# Shield.net
KiCad netlist of a schematic drawn in Altium Designer
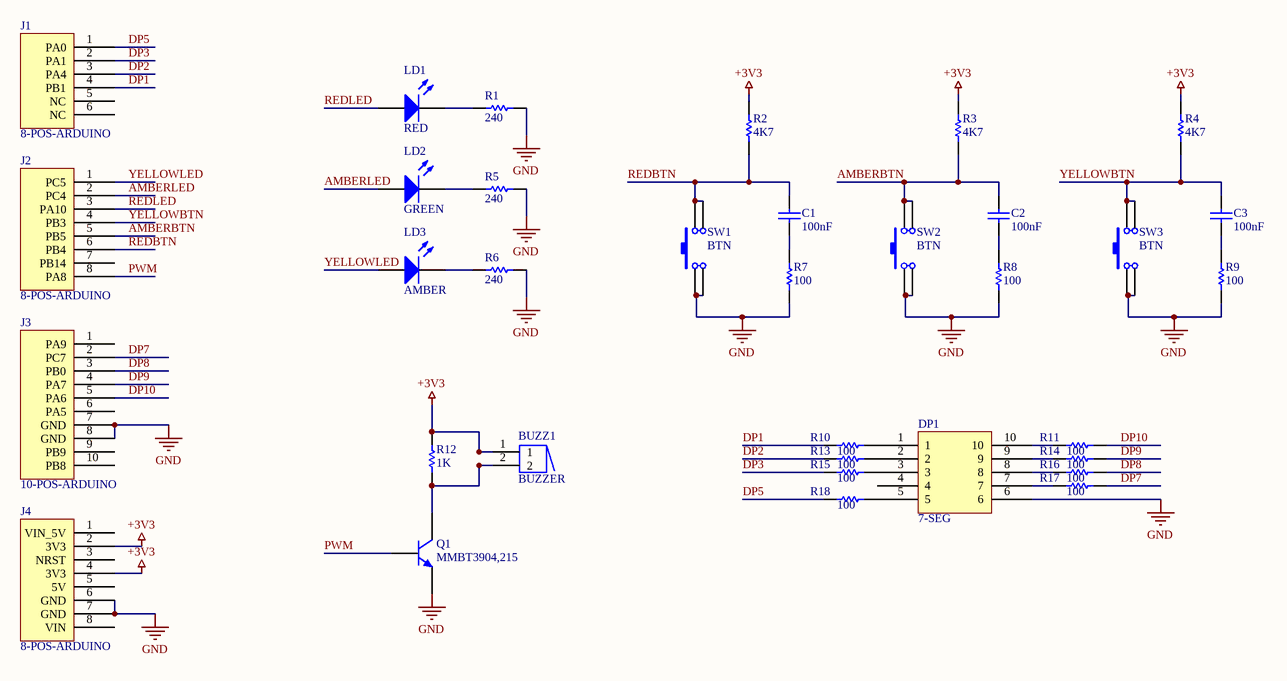
[diagram p0: Shield.SchDoc]

(export (version "E")
  (design (tool "Eeschema 10.0.6"))
  (components
    (comp (ref "BUZZ1")
      (value "BUZZER")
      (footprint "Buzzer")
      (description "AUDIO PIEZO TRANSDUCER 30V TH")
      (fields (field (name "MANUFACTURER") "TDK") (field (name "MANUFACTURER PART NUMBER") "PS1240P02BT"))
      (libsource (lib "Shield") (part "PS1240P02BT"))
    )
    (comp (ref "C1")
      (value "100nF")
      (footprint "CAPCP3225X12N")
      (description "CAP CER 0.1UF 50V X7R 1206")
      (fields
        (field (name "MANUFACTURER") "Yageo")
        (field (name "MANUFACTURER PART NUMBER") "CC1206KRX7R9BB104")
      )
      (libsource (lib "Shield") (part "CC1206KRX7R9BB104"))
    )
    (comp (ref "C2")
      (value "100nF")
      (footprint "CAPCP3225X12N")
      (description "CAP CER 0.1UF 50V X7R 1206")
      (fields
        (field (name "MANUFACTURER") "Yageo")
        (field (name "MANUFACTURER PART NUMBER") "CC1206KRX7R9BB104")
      )
      (libsource (lib "Shield") (part "CC1206KRX7R9BB104"))
    )
    (comp (ref "C3")
      (value "100nF")
      (footprint "CAPCP3225X12N")
      (description "CAP CER 0.1UF 50V X7R 1206")
      (fields
        (field (name "MANUFACTURER") "Yageo")
        (field (name "MANUFACTURER PART NUMBER") "CC1206KRX7R9BB104")
      )
      (libsource (lib "Shield") (part "CC1206KRX7R9BB104"))
    )
    (comp (ref "DP1")
      (value "7-SEG")
      (footprint "7-seg-display")
      (fields
        (field (name "MANUFACTURER") "Inolux")
        (field (name "MANUFACTURER PART NUMBER") "INND-TS40YGCB")
      )
      (libsource (lib "Shield") (part "INND-TS40YGCB"))
    )
    (comp (ref "J1")
      (value "8-POS-ARDUINO")
      (footprint "PIN 6")
      (description "Conn Header Vert 6POS 2.54MM")
      (fields
        (field (name "MANUFACTURER") "Sullins")
        (field (name "MANUFACTURER PART NUMBER") "PREC006SABN-RC")
      )
      (libsource (lib "Shield") (part "PREC006SABN-RC"))
    )
    (comp (ref "J2")
      (value "8-POS-ARDUINO")
      (footprint "PIN 8")
      (description "CONN HEADER VERT 8POS 2.54MM")
      (fields
        (field (name "MANUFACTURER") "Sullins")
        (field (name "MANUFACTURER PART NUMBER") "PREC008SAAN-RC")
      )
      (libsource (lib "Shield") (part "PREC008SAAN-RC"))
    )
    (comp (ref "J3")
      (value "10-POS-ARDUINO")
      (footprint "PIN 10")
      (description "CONN HEADER .100\" SNGL STR 10POS")
      (fields
        (field (name "MANUFACTURER") "Sullins")
        (field (name "MANUFACTURER PART NUMBER") "PREC010SAAN-RC")
      )
      (libsource (lib "Shield") (part "PREC010SAAN-RC"))
    )
    (comp (ref "J4")
      (value "8-POS-ARDUINO")
      (footprint "PIN 8")
      (description "CONN HEADER VERT 8POS 2.54MM")
      (fields
        (field (name "MANUFACTURER") "Sullins")
        (field (name "MANUFACTURER PART NUMBER") "PREC008SAAN-RC")
      )
      (libsource (lib "Shield") (part "PREC008SAAN-RC (2)"))
    )
    (comp (ref "LD1")
      (value "RED")
      (footprint "DIOC3216X21N")
      (description "LED Uni-Color Red 660nm 2-Pin Chip LED T/R")
      (fields
        (field (name "MANUFACTURER") "Vishay Lite-On")
        (field (name "MANUFACTURER PART NUMBER") "LTST-C150CKT")
      )
      (libsource (lib "Shield") (part "LTST-C150CKT"))
    )
    (comp (ref "LD2")
      (value "GREEN")
      (footprint "DIOC3216X21N")
      (description "LED GREEN CLEAR 1206 SMD")
      (fields
        (field (name "MANUFACTURER") "Vishay Lite-On")
        (field (name "MANUFACTURER PART NUMBER") "LTST-C150GKT")
      )
      (libsource (lib "Shield") (part "LTST-C150GKT"))
    )
    (comp (ref "LD3")
      (value "AMBER")
      (footprint "DIOC3216X21N")
      (description "LED AMBER CLEAR 1206 SMD")
      (fields
        (field (name "MANUFACTURER") "Vishay Lite-On")
        (field (name "MANUFACTURER PART NUMBER") "LTST-C150AKT")
      )
      (libsource (lib "Shield") (part "LTST-C150AKT"))
    )
    (comp (ref "Q1")
      (value "MMBT3904,215")
      (footprint "SOT95P230X110-3N")
      (description "TRANS NPN 40V 0.2A SOT23")
      (fields (field (name "MANUFACTURER") "Nexperia"))
      (libsource (lib "Shield") (part "MMBT3904,215"))
    )
    (comp (ref "R1")
      (value "240")
      (footprint "RESC3115X06N")
      (description "Res Thick Film 1206 240 Ohm 1% 0.25W(1/4W) ±100ppm/C Molded SMD Automotive T/R")
      (fields
        (field (name "MANUFACTURER") "Stackpole Electronics")
        (field (name "MANUFACTURER PART NUMBER") "RMCF1206FT240R")
      )
      (libsource (lib "Shield") (part "RMCF1206FT240R"))
    )
    (comp (ref "R2")
      (value "4K7")
      (footprint "RESC3115X06N")
      (description "RES SMD 4.7K OHM 1% 1/4W 1206")
      (fields
        (field (name "MANUFACTURER") "Stackpole Electronics")
        (field (name "MANUFACTURER PART NUMBER") "RMCF1206FT4K70")
      )
      (libsource (lib "Shield") (part "RMCF1206FT4K70"))
    )
    (comp (ref "R3")
      (value "4K7")
      (footprint "RESC3115X06N")
      (description "RES SMD 4.7K OHM 1% 1/4W 1206")
      (fields
        (field (name "MANUFACTURER") "Stackpole Electronics")
        (field (name "MANUFACTURER PART NUMBER") "RMCF1206FT4K70")
      )
      (libsource (lib "Shield") (part "RMCF1206FT4K70"))
    )
    (comp (ref "R4")
      (value "4K7")
      (footprint "RESC3115X06N")
      (description "RES SMD 4.7K OHM 1% 1/4W 1206")
      (fields
        (field (name "MANUFACTURER") "Stackpole Electronics")
        (field (name "MANUFACTURER PART NUMBER") "RMCF1206FT4K70")
      )
      (libsource (lib "Shield") (part "RMCF1206FT4K70"))
    )
    (comp (ref "R5")
      (value "240")
      (footprint "RESC3115X06N")
      (description "Res Thick Film 1206 240 Ohm 1% 0.25W(1/4W) ±100ppm/C Molded SMD Automotive T/R")
      (fields
        (field (name "MANUFACTURER") "Stackpole Electronics")
        (field (name "MANUFACTURER PART NUMBER") "RMCF1206FT240R")
      )
      (libsource (lib "Shield") (part "RMCF1206FT240R"))
    )
    (comp (ref "R6")
      (value "240")
      (footprint "RESC3115X06N")
      (description "Res Thick Film 1206 240 Ohm 1% 0.25W(1/4W) ±100ppm/C Molded SMD Automotive T/R")
      (fields
        (field (name "MANUFACTURER") "Stackpole Electronics")
        (field (name "MANUFACTURER PART NUMBER") "RMCF1206FT240R")
      )
      (libsource (lib "Shield") (part "RMCF1206FT240R"))
    )
    (comp (ref "R7")
      (value "100")
      (footprint "RESC3115X06N")
      (description "RES 100 OHM 1% 1/4W 1206")
      (fields
        (field (name "MANUFACTURER") "Stackpole Electronics")
        (field (name "MANUFACTURER PART NUMBER") "RMCF1206FT100R")
      )
      (libsource (lib "Shield") (part "RMCF1206FT100R"))
    )
    (comp (ref "R8")
      (value "100")
      (footprint "RESC3115X06N")
      (description "RES 100 OHM 1% 1/4W 1206")
      (fields
        (field (name "MANUFACTURER") "Stackpole Electronics")
        (field (name "MANUFACTURER PART NUMBER") "RMCF1206FT100R")
      )
      (libsource (lib "Shield") (part "RMCF1206FT100R"))
    )
    (comp (ref "R9")
      (value "100")
      (footprint "RESC3115X06N")
      (description "RES 100 OHM 1% 1/4W 1206")
      (fields
        (field (name "MANUFACTURER") "Stackpole Electronics")
        (field (name "MANUFACTURER PART NUMBER") "RMCF1206FT100R")
      )
      (libsource (lib "Shield") (part "RMCF1206FT100R"))
    )
    (comp (ref "R10")
      (value "100")
      (footprint "RESC3115X06N")
      (description "RES 100 OHM 1% 1/4W 1206")
      (fields
        (field (name "MANUFACTURER") "Stackpole Electronics")
        (field (name "MANUFACTURER PART NUMBER") "RMCF1206FT100R")
      )
      (libsource (lib "Shield") (part "RMCF1206FT100R"))
    )
    (comp (ref "R11")
      (value "100")
      (footprint "RESC3115X06N")
      (description "RES 100 OHM 1% 1/4W 1206")
      (fields
        (field (name "MANUFACTURER") "Stackpole Electronics")
        (field (name "MANUFACTURER PART NUMBER") "RMCF1206FT100R")
      )
      (libsource (lib "Shield") (part "RMCF1206FT100R"))
    )
    (comp (ref "R12")
      (value "1K")
      (footprint "RESC3115X06N")
      (description "RES 1K OHM 1% 1/2W 1206")
      (fields
        (field (name "MANUFACTURER") "Stackpole Electronics")
        (field (name "MANUFACTURER PART NUMBER") "RNCP1206FTD1K00")
      )
      (libsource (lib "Shield") (part "RNCP1206FTD1K00"))
    )
    (comp (ref "R13")
      (value "100")
      (footprint "RESC3115X06N")
      (description "RES 100 OHM 1% 1/4W 1206")
      (fields
        (field (name "MANUFACTURER") "Stackpole Electronics")
        (field (name "MANUFACTURER PART NUMBER") "RMCF1206FT100R")
      )
      (libsource (lib "Shield") (part "RMCF1206FT100R"))
    )
    (comp (ref "R14")
      (value "100")
      (footprint "RESC3115X06N")
      (description "RES 100 OHM 1% 1/4W 1206")
      (fields
        (field (name "MANUFACTURER") "Stackpole Electronics")
        (field (name "MANUFACTURER PART NUMBER") "RMCF1206FT100R")
      )
      (libsource (lib "Shield") (part "RMCF1206FT100R"))
    )
    (comp (ref "R15")
      (value "100")
      (footprint "RESC3115X06N")
      (description "RES 100 OHM 1% 1/4W 1206")
      (fields
        (field (name "MANUFACTURER") "Stackpole Electronics")
        (field (name "MANUFACTURER PART NUMBER") "RMCF1206FT100R")
      )
      (libsource (lib "Shield") (part "RMCF1206FT100R"))
    )
    (comp (ref "R16")
      (value "100")
      (footprint "RESC3115X06N")
      (description "RES 100 OHM 1% 1/4W 1206")
      (fields
        (field (name "MANUFACTURER") "Stackpole Electronics")
        (field (name "MANUFACTURER PART NUMBER") "RMCF1206FT100R")
      )
      (libsource (lib "Shield") (part "RMCF1206FT100R"))
    )
    (comp (ref "R17")
      (value "100")
      (footprint "RESC3115X06N")
      (description "RES 100 OHM 1% 1/4W 1206")
      (fields
        (field (name "MANUFACTURER") "Stackpole Electronics")
        (field (name "MANUFACTURER PART NUMBER") "RMCF1206FT100R")
      )
      (libsource (lib "Shield") (part "RMCF1206FT100R"))
    )
    (comp (ref "R18")
      (value "100")
      (footprint "RESC3115X06N")
      (description "RES 100 OHM 1% 1/4W 1206")
      (fields
        (field (name "MANUFACTURER") "Stackpole Electronics")
        (field (name "MANUFACTURER PART NUMBER") "RMCF1206FT100R")
      )
      (libsource (lib "Shield") (part "RMCF1206FT100R"))
    )
    (comp (ref "SW1")
      (value "BTN")
      (footprint "Button")
      (description "INWALL LENS COVER , WHITE , 6 (")
      (fields
        (field (name "MANUFACTURER") "ITT C&K")
        (field (name "MANUFACTURER PART NUMBER") "PTS647SK70SMTR2LFS")
      )
      (libsource (lib "Shield") (part "PTS647SK70SMTR2LFS"))
    )
    (comp (ref "SW2")
      (value "BTN")
      (footprint "Button")
      (description "INWALL LENS COVER , WHITE , 6 (")
      (fields
        (field (name "MANUFACTURER") "ITT C&K")
        (field (name "MANUFACTURER PART NUMBER") "PTS647SK70SMTR2LFS")
      )
      (libsource (lib "Shield") (part "PTS647SK70SMTR2LFS"))
    )
    (comp (ref "SW3")
      (value "BTN")
      (footprint "Button")
      (description "INWALL LENS COVER , WHITE , 6 (")
      (fields
        (field (name "MANUFACTURER") "ITT C&K")
        (field (name "MANUFACTURER PART NUMBER") "PTS647SK70SMTR2LFS")
      )
      (libsource (lib "Shield") (part "PTS647SK70SMTR2LFS"))
    )
  )
  (nets
    (net (code "1") (name "+3V3") (class "Default")
      (node (ref "BUZZ1") (pin "1") (pinfunction "1_1") (pintype "passive"))
      (node (ref "J4") (pin "2") (pinfunction "3V3_2") (pintype "passive"))
      (node (ref "J4") (pin "4") (pinfunction "3V3_4") (pintype "passive"))
      (node (ref "R12") (pin "2") (pinfunction "2_2") (pintype "passive"))
      (node (ref "R2") (pin "2") (pinfunction "2_2") (pintype "passive"))
      (node (ref "R3") (pin "2") (pinfunction "2_2") (pintype "passive"))
      (node (ref "R4") (pin "2") (pinfunction "2_2") (pintype "passive"))
    )
    (net (code "2") (name "/AMBERBTN") (class "Default")
      (node (ref "C2") (pin "2") (pinfunction "2_2") (pintype "passive"))
      (node (ref "J2") (pin "5") (pinfunction "PB5_5") (pintype "passive"))
      (node (ref "R3") (pin "1") (pinfunction "1_1") (pintype "passive"))
      (node (ref "SW2") (pin "3") (pinfunction "2_3") (pintype "passive"))
      (node (ref "SW2") (pin "4") (pinfunction "3_4") (pintype "passive"))
    )
    (net (code "3") (name "/AMBERLED") (class "Default")
      (node (ref "J2") (pin "2") (pinfunction "PC4_2") (pintype "passive"))
      (node (ref "LD2") (pin "1") (pinfunction "A_1") (pintype "passive"))
    )
    (net (code "4") (name "/DP1") (class "Default")
      (node (ref "J1") (pin "4") (pinfunction "PB1_4") (pintype "passive"))
      (node (ref "R10") (pin "2") (pinfunction "2_2") (pintype "passive"))
    )
    (net (code "5") (name "/DP2") (class "Default")
      (node (ref "J1") (pin "3") (pinfunction "PA4_3") (pintype "passive"))
      (node (ref "R13") (pin "2") (pinfunction "2_2") (pintype "passive"))
    )
    (net (code "6") (name "/DP3") (class "Default")
      (node (ref "J1") (pin "2") (pinfunction "PA1_2") (pintype "passive"))
      (node (ref "R15") (pin "2") (pinfunction "2_2") (pintype "passive"))
    )
    (net (code "7") (name "/DP5") (class "Default")
      (node (ref "J1") (pin "1") (pinfunction "PA0_1") (pintype "passive"))
      (node (ref "R18") (pin "2") (pinfunction "2_2") (pintype "passive"))
    )
    (net (code "8") (name "/DP7") (class "Default")
      (node (ref "J3") (pin "2") (pinfunction "PC7_2") (pintype "passive"))
      (node (ref "R17") (pin "1") (pinfunction "1_1") (pintype "passive"))
    )
    (net (code "9") (name "/DP8") (class "Default")
      (node (ref "J3") (pin "3") (pinfunction "PB0_3") (pintype "passive"))
      (node (ref "R16") (pin "1") (pinfunction "1_1") (pintype "passive"))
    )
    (net (code "10") (name "/DP9") (class "Default")
      (node (ref "J3") (pin "4") (pinfunction "PA7_4") (pintype "passive"))
      (node (ref "R14") (pin "1") (pinfunction "1_1") (pintype "passive"))
    )
    (net (code "11") (name "/DP10") (class "Default")
      (node (ref "J3") (pin "5") (pinfunction "PA6_5") (pintype "passive"))
      (node (ref "R11") (pin "1") (pinfunction "1_1") (pintype "passive"))
    )
    (net (code "12") (name "/PWM") (class "Default")
      (node (ref "J2") (pin "8") (pinfunction "PA8_8") (pintype "passive"))
      (node (ref "Q1") (pin "1") (pinfunction "B_1") (pintype "passive"))
    )
    (net (code "13") (name "/REDBTN") (class "Default")
      (node (ref "C1") (pin "2") (pinfunction "2_2") (pintype "passive"))
      (node (ref "J2") (pin "6") (pinfunction "PB4_6") (pintype "passive"))
      (node (ref "R2") (pin "1") (pinfunction "1_1") (pintype "passive"))
      (node (ref "SW1") (pin "3") (pinfunction "2_3") (pintype "passive"))
      (node (ref "SW1") (pin "4") (pinfunction "3_4") (pintype "passive"))
    )
    (net (code "14") (name "/REDLED") (class "Default")
      (node (ref "J2") (pin "3") (pinfunction "PA10_3") (pintype "passive"))
      (node (ref "LD1") (pin "1") (pinfunction "A_1") (pintype "passive"))
    )
    (net (code "15") (name "/YELLOWBTN") (class "Default")
      (node (ref "C3") (pin "2") (pinfunction "2_2") (pintype "passive"))
      (node (ref "J2") (pin "4") (pinfunction "PB3_4") (pintype "passive"))
      (node (ref "R4") (pin "1") (pinfunction "1_1") (pintype "passive"))
      (node (ref "SW3") (pin "3") (pinfunction "2_3") (pintype "passive"))
      (node (ref "SW3") (pin "4") (pinfunction "3_4") (pintype "passive"))
    )
    (net (code "16") (name "/YELLOWLED") (class "Default")
      (node (ref "J2") (pin "1") (pinfunction "PC5_1") (pintype "passive"))
      (node (ref "LD3") (pin "1") (pinfunction "A_1") (pintype "passive"))
    )
    (net (code "17") (name "GND") (class "Default")
      (node (ref "DP1") (pin "6") (pinfunction "6_6") (pintype "passive"))
      (node (ref "J3") (pin "7") (pinfunction "GND_7") (pintype "passive"))
      (node (ref "J3") (pin "8") (pinfunction "GND_8") (pintype "passive"))
      (node (ref "J4") (pin "6") (pinfunction "GND_6") (pintype "passive"))
      (node (ref "J4") (pin "7") (pinfunction "GND_7") (pintype "passive"))
      (node (ref "Q1") (pin "2") (pinfunction "E_2") (pintype "passive"))
      (node (ref "R1") (pin "2") (pinfunction "2_2") (pintype "passive"))
      (node (ref "R5") (pin "2") (pinfunction "2_2") (pintype "passive"))
      (node (ref "R6") (pin "2") (pinfunction "2_2") (pintype "passive"))
      (node (ref "R7") (pin "1") (pinfunction "1_1") (pintype "passive"))
      (node (ref "R8") (pin "1") (pinfunction "1_1") (pintype "passive"))
      (node (ref "R9") (pin "1") (pinfunction "1_1") (pintype "passive"))
      (node (ref "SW1") (pin "1") (pinfunction "1_1") (pintype "passive"))
      (node (ref "SW1") (pin "2") (pinfunction "1_2") (pintype "passive"))
      (node (ref "SW2") (pin "1") (pinfunction "1_1") (pintype "passive"))
      (node (ref "SW2") (pin "2") (pinfunction "1_2") (pintype "passive"))
      (node (ref "SW3") (pin "1") (pinfunction "1_1") (pintype "passive"))
      (node (ref "SW3") (pin "2") (pinfunction "1_2") (pintype "passive"))
    )
    (net (code "18") (name "Net-(C1-Pad1)") (class "Default")
      (node (ref "C1") (pin "1") (pinfunction "1_1") (pintype "passive"))
      (node (ref "R7") (pin "2") (pinfunction "2_2") (pintype "passive"))
    )
    (net (code "19") (name "Net-(C2-Pad1)") (class "Default")
      (node (ref "C2") (pin "1") (pinfunction "1_1") (pintype "passive"))
      (node (ref "R8") (pin "2") (pinfunction "2_2") (pintype "passive"))
    )
    (net (code "20") (name "Net-(C3-Pad1)") (class "Default")
      (node (ref "C3") (pin "1") (pinfunction "1_1") (pintype "passive"))
      (node (ref "R9") (pin "2") (pinfunction "2_2") (pintype "passive"))
    )
    (net (code "21") (name "Net-(DP1-Pad1)") (class "Default")
      (node (ref "DP1") (pin "1") (pinfunction "1_1") (pintype "passive"))
      (node (ref "R10") (pin "1") (pinfunction "1_1") (pintype "passive"))
    )
    (net (code "22") (name "Net-(DP1-Pad2)") (class "Default")
      (node (ref "DP1") (pin "2") (pinfunction "2_2") (pintype "passive"))
      (node (ref "R13") (pin "1") (pinfunction "1_1") (pintype "passive"))
    )
    (net (code "23") (name "Net-(DP1-Pad3)") (class "Default")
      (node (ref "DP1") (pin "3") (pinfunction "3_3") (pintype "passive"))
      (node (ref "R15") (pin "1") (pinfunction "1_1") (pintype "passive"))
    )
    (net (code "24") (name "Net-(DP1-Pad5)") (class "Default")
      (node (ref "DP1") (pin "5") (pinfunction "5_5") (pintype "passive"))
      (node (ref "R18") (pin "1") (pinfunction "1_1") (pintype "passive"))
    )
    (net (code "25") (name "Net-(DP1-Pad7)") (class "Default")
      (node (ref "DP1") (pin "7") (pinfunction "7_7") (pintype "passive"))
      (node (ref "R17") (pin "2") (pinfunction "2_2") (pintype "passive"))
    )
    (net (code "26") (name "Net-(DP1-Pad8)") (class "Default")
      (node (ref "DP1") (pin "8") (pinfunction "8_8") (pintype "passive"))
      (node (ref "R16") (pin "2") (pinfunction "2_2") (pintype "passive"))
    )
    (net (code "27") (name "Net-(DP1-Pad9)") (class "Default")
      (node (ref "DP1") (pin "9") (pinfunction "9_9") (pintype "passive"))
      (node (ref "R14") (pin "2") (pinfunction "2_2") (pintype "passive"))
    )
    (net (code "28") (name "Net-(DP1-Pad10)") (class "Default")
      (node (ref "DP1") (pin "10") (pinfunction "10_10") (pintype "passive"))
      (node (ref "R11") (pin "2") (pinfunction "2_2") (pintype "passive"))
    )
    (net (code "29") (name "Net-(LD1-K)") (class "Default")
      (node (ref "LD1") (pin "2") (pinfunction "K_2") (pintype "passive"))
      (node (ref "R1") (pin "1") (pinfunction "1_1") (pintype "passive"))
    )
    (net (code "30") (name "Net-(LD2-K)") (class "Default")
      (node (ref "LD2") (pin "2") (pinfunction "K_2") (pintype "passive"))
      (node (ref "R5") (pin "1") (pinfunction "1_1") (pintype "passive"))
    )
    (net (code "31") (name "Net-(LD3-K)") (class "Default")
      (node (ref "LD3") (pin "2") (pinfunction "K_2") (pintype "passive"))
      (node (ref "R6") (pin "1") (pinfunction "1_1") (pintype "passive"))
    )
    (net (code "32") (name "Net-(Q1-C)") (class "Default")
      (node (ref "BUZZ1") (pin "2") (pinfunction "2_2") (pintype "passive"))
      (node (ref "Q1") (pin "3") (pinfunction "C_3") (pintype "passive"))
      (node (ref "R12") (pin "1") (pinfunction "1_1") (pintype "passive"))
    )
    (net (code "33") (name "unconnected-(DP1-Pad4)") (class "Default")
      (node (ref "DP1") (pin "4") (pinfunction "4_4") (pintype "passive"))
    )
    (net (code "34") (name "unconnected-(J1-NC-Pad5)") (class "Default")
      (node (ref "J1") (pin "5") (pinfunction "NC_5") (pintype "passive"))
    )
    (net (code "35") (name "unconnected-(J1-NC-Pad6)") (class "Default")
      (node (ref "J1") (pin "6") (pinfunction "NC_6") (pintype "passive"))
    )
    (net (code "36") (name "unconnected-(J2-PB14-Pad7)") (class "Default")
      (node (ref "J2") (pin "7") (pinfunction "PB14_7") (pintype "passive"))
    )
    (net (code "37") (name "unconnected-(J3-PA5-Pad6)") (class "Default")
      (node (ref "J3") (pin "6") (pinfunction "PA5_6") (pintype "passive"))
    )
    (net (code "38") (name "unconnected-(J3-PA9-Pad1)") (class "Default")
      (node (ref "J3") (pin "1") (pinfunction "PA9_1") (pintype "passive"))
    )
    (net (code "39") (name "unconnected-(J3-PB8-Pad10)") (class "Default")
      (node (ref "J3") (pin "10") (pinfunction "PB8_10") (pintype "passive"))
    )
    (net (code "40") (name "unconnected-(J3-PB9-Pad9)") (class "Default")
      (node (ref "J3") (pin "9") (pinfunction "PB9_9") (pintype "passive"))
    )
    (net (code "41") (name "unconnected-(J4-5V-Pad5)") (class "Default")
      (node (ref "J4") (pin "5") (pinfunction "5V_5") (pintype "passive"))
    )
    (net (code "42") (name "unconnected-(J4-NRST-Pad3)") (class "Default")
      (node (ref "J4") (pin "3") (pinfunction "NRST_3") (pintype "passive"))
    )
    (net (code "43") (name "unconnected-(J4-VIN-Pad8)") (class "Default")
      (node (ref "J4") (pin "8") (pinfunction "VIN_8") (pintype "passive"))
    )
    (net (code "44") (name "unconnected-(J4-VIN_5V-Pad1)") (class "Default")
      (node (ref "J4") (pin "1") (pinfunction "VIN_5V_1") (pintype "passive"))
    )
  )
)
